# T5400_Barometer_Breakout.net
KiCad netlist of a schematic drawn in EAGLE
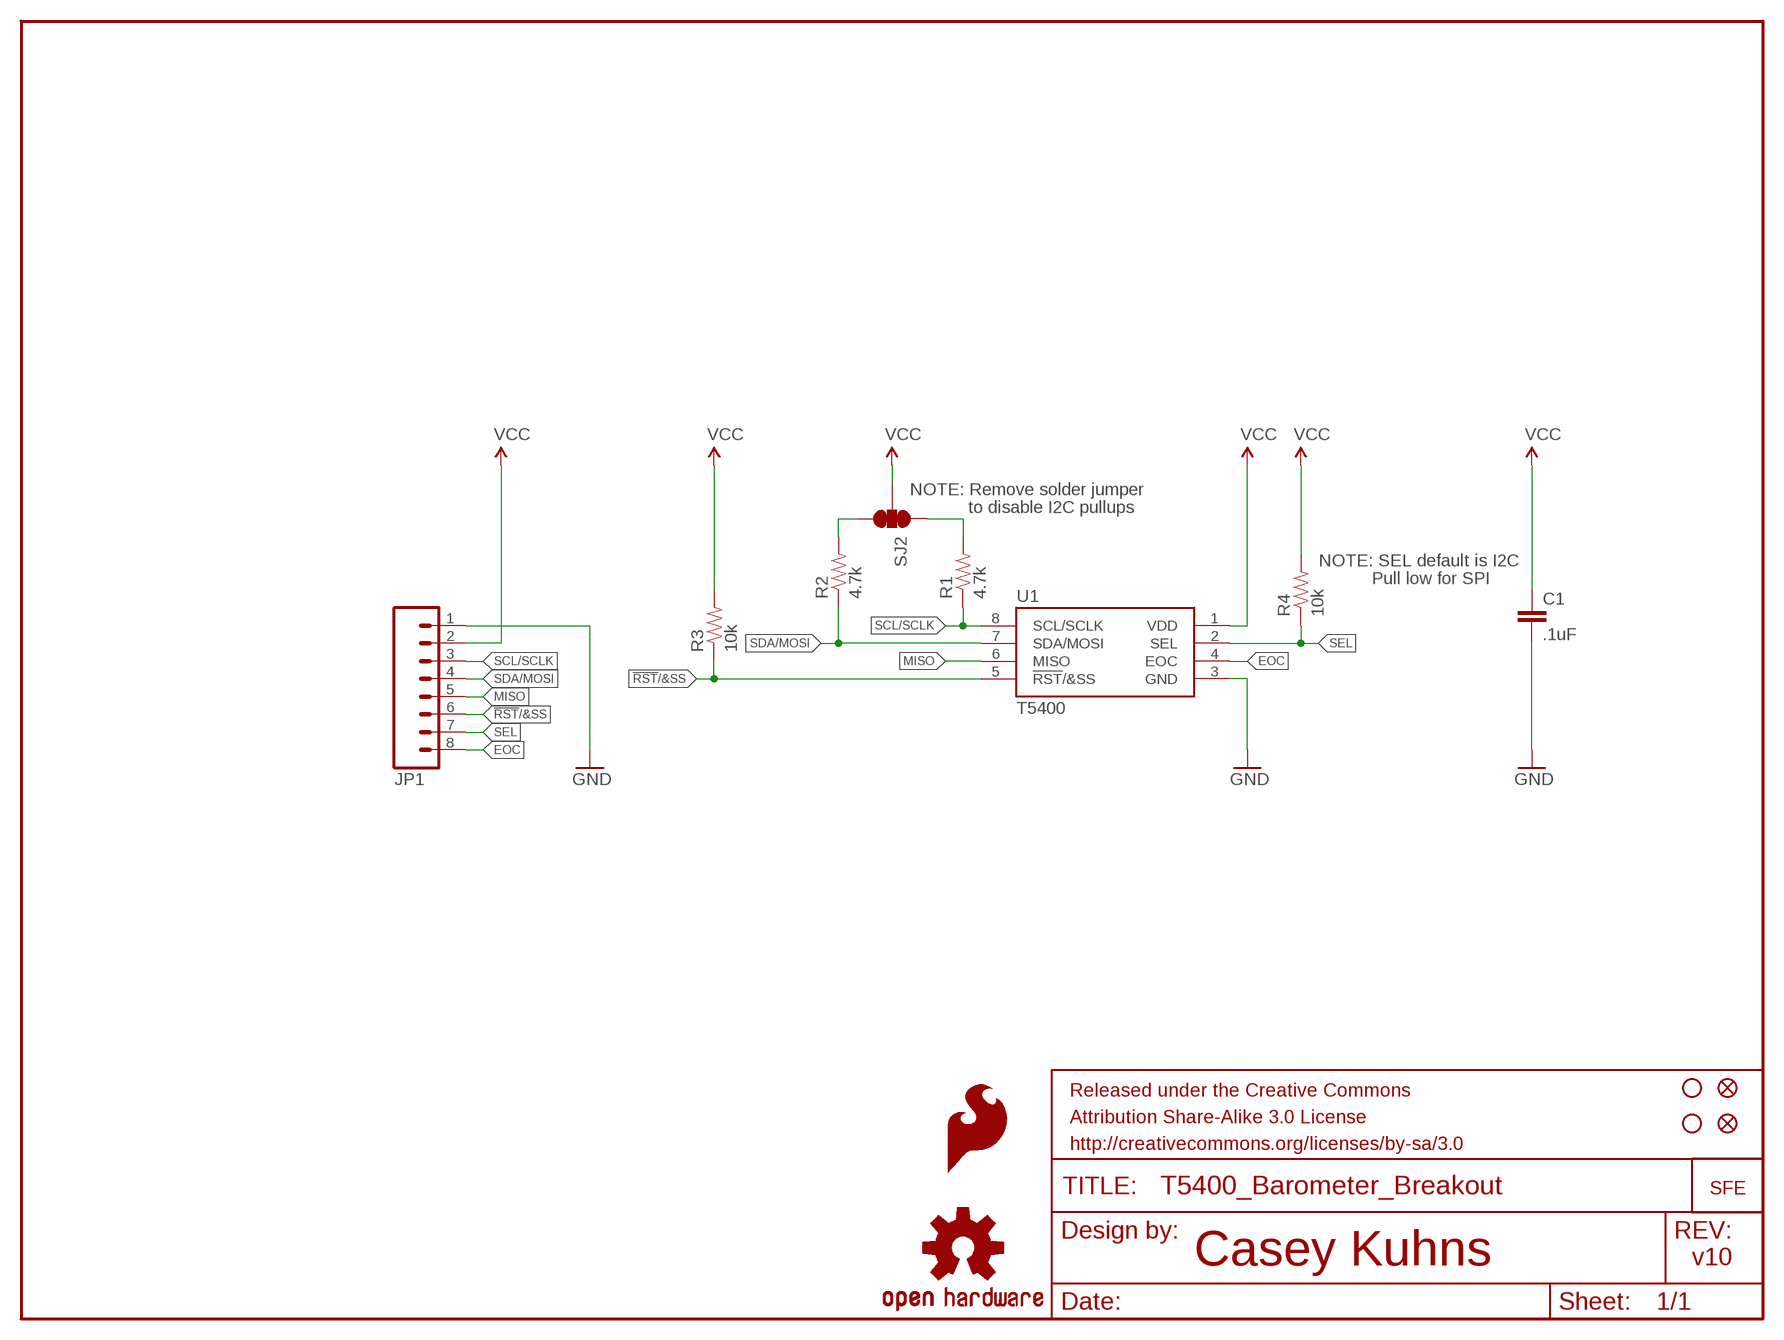
[diagram p0: schematic, sheet 1]

(export (version "E")
  (design (tool "Eeschema 10.0.6"))
  (components
    (comp (ref "C1")
      (value ".1uF")
      (footprint "eagle-import:0603-CAP")
      (libsource (lib "eagle-import") (part "0.1UF-25V-5%(0603)"))
    )
    (comp (ref "FID1")
      (value "FIDUCIAL1X2")
      (footprint "eagle-import:FIDUCIAL-1X2")
      (libsource (lib "eagle-import") (part "FIDUCIAL1X2"))
    )
    (comp (ref "FID2")
      (value "FIDUCIAL1X2")
      (footprint "eagle-import:FIDUCIAL-1X2")
      (libsource (lib "eagle-import") (part "FIDUCIAL1X2"))
    )
    (comp (ref "FRAME1")
      (value "FRAME-LETTER")
      (footprint "eagle-import:CREATIVE_COMMONS")
      (libsource (lib "eagle-import") (part "FRAME-LETTER"))
    )
    (comp (ref "JP1")
      (value "M081X08")
      (footprint "eagle-import:1X08")
      (libsource (lib "eagle-import") (part "M081X08"))
    )
    (comp (ref "LOGO1")
      (value "LOGO-SFENEW")
      (footprint "eagle-import:SFE-NEW-WEBLOGO")
      (libsource (lib "eagle-import") (part "LOGO-SFENEW"))
    )
    (comp (ref "LOGO2")
      (value "OSHW-LOGOS")
      (footprint "eagle-import:OSHW-LOGO-S")
      (libsource (lib "eagle-import") (part "OSHW-LOGOS"))
    )
    (comp (ref "LOGO3")
      (value "SFE_LOGO_FLAME.1_INCH")
      (footprint "eagle-import:SFE_LOGO_FLAME_.1")
      (libsource (lib "eagle-import") (part "SFE_LOGO_FLAME.1_INCH"))
    )
    (comp (ref "R1")
      (value "4.7k")
      (footprint "eagle-import:0603-RES")
      (libsource (lib "eagle-import") (part "RESISTOR0603-RES"))
    )
    (comp (ref "R2")
      (value "4.7k")
      (footprint "eagle-import:0603-RES")
      (libsource (lib "eagle-import") (part "RESISTOR0603-RES"))
    )
    (comp (ref "R3")
      (value "10k")
      (footprint "eagle-import:0603-RES")
      (libsource (lib "eagle-import") (part "RESISTOR0603-RES"))
    )
    (comp (ref "R4")
      (value "10k")
      (footprint "eagle-import:0603-RES")
      (libsource (lib "eagle-import") (part "RESISTOR0603-RES"))
    )
    (comp (ref "SJ2")
      (value "SOLDERJUMPER_2WAYPASTE1&2&3")
      (footprint "eagle-import:SJ_3_PASTE1&2&3")
      (libsource (lib "eagle-import") (part "SOLDERJUMPER_2WAYPASTE1&2&3"))
    )
    (comp (ref "STANDOFF1")
      (value "STAND-OFF")
      (footprint "eagle-import:STAND-OFF")
      (libsource (lib "eagle-import") (part "STAND-OFF"))
    )
    (comp (ref "STANDOFF2")
      (value "STAND-OFF")
      (footprint "eagle-import:STAND-OFF")
      (libsource (lib "eagle-import") (part "STAND-OFF"))
    )
    (comp (ref "U1")
      (value "T5400")
      (footprint "eagle-import:T5400")
      (libsource (lib "eagle-import") (part "T5400"))
    )
  )
  (nets
    (net (code "1") (name "/~{RST}{slash}&SS") (class "Default")
      (node (ref "JP1") (pin "6") (pinfunction "6_6") (pintype "passive"))
      (node (ref "R3") (pin "1") (pinfunction "1_1") (pintype "passive"))
      (node (ref "U1") (pin "5") (pinfunction "~{RST}/&SS_5") (pintype "bidirectional"))
    )
    (net (code "2") (name "EOC") (class "Default")
      (node (ref "JP1") (pin "8") (pinfunction "8_8") (pintype "passive"))
      (node (ref "U1") (pin "4") (pinfunction "EOC_4") (pintype "bidirectional"))
    )
    (net (code "3") (name "GND") (class "Default")
      (node (ref "C1") (pin "2") (pinfunction "2_2") (pintype "passive"))
      (node (ref "JP1") (pin "1") (pinfunction "1_1") (pintype "passive"))
      (node (ref "U1") (pin "3") (pinfunction "GND_3") (pintype "bidirectional"))
    )
    (net (code "4") (name "MISO") (class "Default")
      (node (ref "JP1") (pin "5") (pinfunction "5_5") (pintype "passive"))
      (node (ref "U1") (pin "6") (pinfunction "MISO_6") (pintype "bidirectional"))
    )
    (net (code "5") (name "Net-(R1-Pad2)") (class "Default")
      (node (ref "R1") (pin "2") (pinfunction "2_2") (pintype "passive"))
      (node (ref "SJ2") (pin "1") (pinfunction "1_1") (pintype "passive"))
    )
    (net (code "6") (name "Net-(R2-Pad2)") (class "Default")
      (node (ref "R2") (pin "2") (pinfunction "2_2") (pintype "passive"))
      (node (ref "SJ2") (pin "3") (pinfunction "3_3") (pintype "passive"))
    )
    (net (code "7") (name "SCL{slash}SCLK") (class "Default")
      (node (ref "JP1") (pin "3") (pinfunction "3_3") (pintype "passive"))
      (node (ref "R1") (pin "1") (pinfunction "1_1") (pintype "passive"))
      (node (ref "U1") (pin "8") (pinfunction "SCL/SCLK_8") (pintype "bidirectional"))
    )
    (net (code "8") (name "SDA{slash}MOSI") (class "Default")
      (node (ref "JP1") (pin "4") (pinfunction "4_4") (pintype "passive"))
      (node (ref "R2") (pin "1") (pinfunction "1_1") (pintype "passive"))
      (node (ref "U1") (pin "7") (pinfunction "SDA/MOSI_7") (pintype "bidirectional"))
    )
    (net (code "9") (name "SEL") (class "Default")
      (node (ref "JP1") (pin "7") (pinfunction "7_7") (pintype "passive"))
      (node (ref "R4") (pin "1") (pinfunction "1_1") (pintype "passive"))
      (node (ref "U1") (pin "2") (pinfunction "SEL_2") (pintype "bidirectional"))
    )
    (net (code "10") (name "VCC") (class "Default")
      (node (ref "C1") (pin "1") (pinfunction "1_1") (pintype "passive"))
      (node (ref "JP1") (pin "2") (pinfunction "2_2") (pintype "passive"))
      (node (ref "R3") (pin "2") (pinfunction "2_2") (pintype "passive"))
      (node (ref "R4") (pin "2") (pinfunction "2_2") (pintype "passive"))
      (node (ref "SJ2") (pin "2") (pinfunction "2_2") (pintype "passive"))
      (node (ref "U1") (pin "1") (pinfunction "VDD_1") (pintype "bidirectional"))
    )
  )
)
